# Battery_charger.net
KiCad netlist of a schematic drawn in Altium Designer
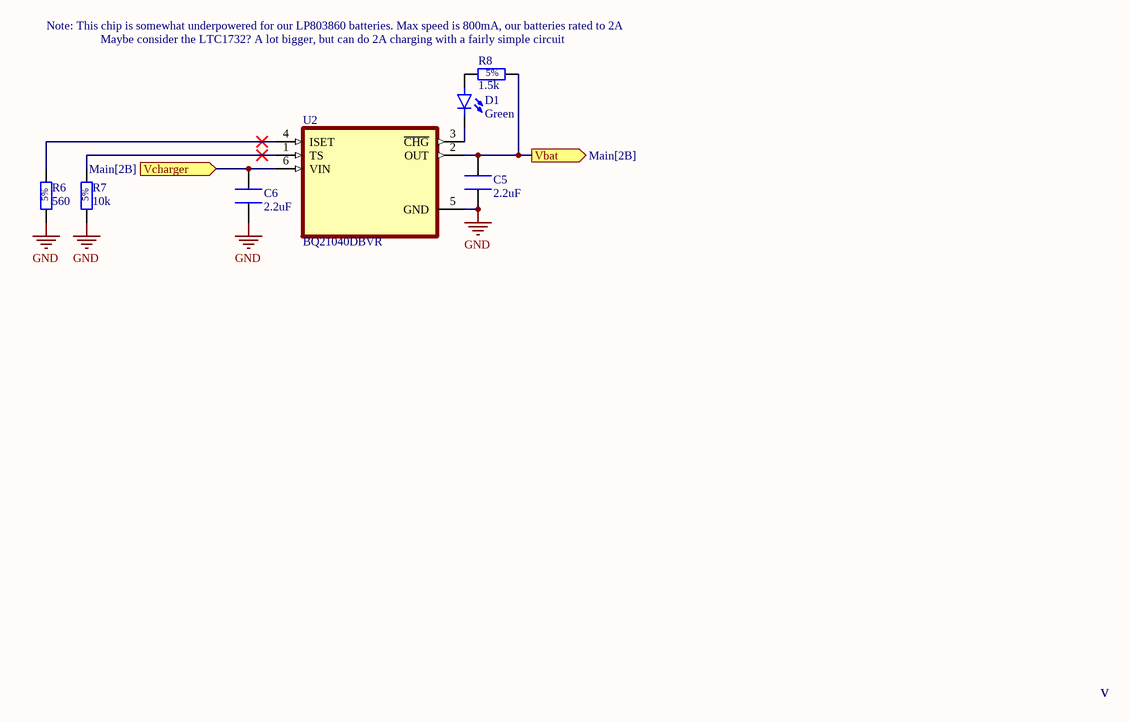
[diagram p0: Battery charger.SchDoc]

(export (version "E")
  (design (tool "Eeschema 10.0.6"))
  (components
    (comp (ref "C5")
      (value "2.2uF")
      (footprint "APSS Prototype Parts:CAPACITOR_0805_2012M-70N")
      (fields
        (field (name "TOLERANCE") "±10%")
        (field (name "MF PART NO.") "C0805C225K8PACTU")
        (field (name "APSS STANDARD PART") "APSS Standard")
      )
      (libsource (lib "APSS Prototype Parts") (part "C0805C225K8PACTU"))
    )
    (comp (ref "C6")
      (value "2.2uF")
      (footprint "APSS Prototype Parts:CAPACITOR_0805_2012M-70N")
      (fields
        (field (name "TOLERANCE") "±10%")
        (field (name "MF PART NO.") "C0805C225K8PACTU")
        (field (name "APSS STANDARD PART") "APSS Standard")
      )
      (libsource (lib "") (part "C0805C225K8PACTU_1"))
    )
    (comp (ref "D1")
      (value "LTST-C190 Series")
      (footprint "APSS Prototype Parts:LED_0603_1608M_0.80mm")
      (description "Diode - LED, 0603")
      (fields
        (field (name "MF PART NO.") "LTST-C190KGKT")
        (field (name "COLOUR") "Green")
        (field (name "APSS STANDARD PART") "APSS Standard")
      )
      (libsource (lib "APSS Prototype Parts") (part "LTST-C190 Series"))
    )
    (comp (ref "R6")
      (value "560")
      (footprint "APSS Flight Parts:Resistor_0805_2012M-50N")
      (fields
        (field (name "TOLERANCE") "5%")
        (field (name "POWER") "1/8W")
        (field (name "MF PART NO.") "RMCF0805JT560R")
      )
      (libsource (lib "APSS Prototype Parts") (part "RMCF0805JT Series"))
    )
    (comp (ref "R7")
      (value "10k")
      (footprint "APSS Flight Parts:Resistor_0805_2012M-50N")
      (fields
        (field (name "TOLERANCE") "5%")
        (field (name "POWER") "1/8W")
        (field (name "MF PART NO.") "RMCF0805JT10K0")
      )
      (libsource (lib "APSS Prototype Parts") (part "RMCF0805JT Series"))
    )
    (comp (ref "R8")
      (value "1.5k")
      (footprint "APSS Flight Parts:Resistor_0805_2012M-50N")
      (fields
        (field (name "TOLERANCE") "5%")
        (field (name "POWER") "1/8W")
        (field (name "MF PART NO.") "RMCF0805JT1K50")
      )
      (libsource (lib "") (part "RMCF0805JT Series_1"))
    )
    (comp (ref "U2")
      (value "BQ21040DBVR")
      (footprint "SOT95P280X145-6N")
      (description "1-cell, 0.8-A Li-ion and Li-polymer battery charger")
      (fields (field (name "MF") "Texas Instruments"))
      (libsource (lib "BQ21040DBVR") (part "BQ21040DBVR"))
    )
  )
  (nets
    (net (code "1") (name "/Vbat") (class "Default")
      (node (ref "C5") (pin "1") (pinfunction "1_1") (pintype "passive"))
      (node (ref "R8") (pin "2") (pinfunction "2_2") (pintype "passive"))
      (node (ref "U2") (pin "2") (pinfunction "OUT_2") (pintype "output"))
    )
    (net (code "2") (name "/Vcharger") (class "Default")
      (node (ref "C6") (pin "2") (pinfunction "2_2") (pintype "passive"))
      (node (ref "U2") (pin "6") (pinfunction "VIN_6") (pintype "input"))
    )
    (net (code "3") (name "GND") (class "Default")
      (node (ref "C5") (pin "2") (pinfunction "2_2") (pintype "passive"))
      (node (ref "C6") (pin "1") (pinfunction "1_1") (pintype "passive"))
      (node (ref "R6") (pin "1") (pinfunction "1_1") (pintype "passive"))
      (node (ref "R7") (pin "1") (pinfunction "1_1") (pintype "passive"))
      (node (ref "U2") (pin "5") (pinfunction "GND_5") (pintype "power_in"))
    )
    (net (code "4") (name "Net-(D1-PadA)") (class "Default")
      (node (ref "D1") (pin "A") (pinfunction "A_A") (pintype "passive"))
      (node (ref "R8") (pin "1") (pinfunction "1_1") (pintype "passive"))
    )
    (net (code "5") (name "Net-(U2-ISET)") (class "Default")
      (node (ref "R6") (pin "2") (pinfunction "2_2") (pintype "passive"))
      (node (ref "U2") (pin "4") (pinfunction "ISET_4") (pintype "input"))
    )
    (net (code "6") (name "Net-(U2-TS)") (class "Default")
      (node (ref "R7") (pin "2") (pinfunction "2_2") (pintype "passive"))
      (node (ref "U2") (pin "1") (pinfunction "TS_1") (pintype "input"))
    )
    (net (code "7") (name "Net-(U2-~{CHG})") (class "Default")
      (node (ref "D1") (pin "C") (pinfunction "C_C") (pintype "passive"))
      (node (ref "U2") (pin "3") (pinfunction "~{CHG}_3") (pintype "output"))
    )
  )
)
